# POWER.net
KiCad netlist of a schematic drawn in Altium Designer
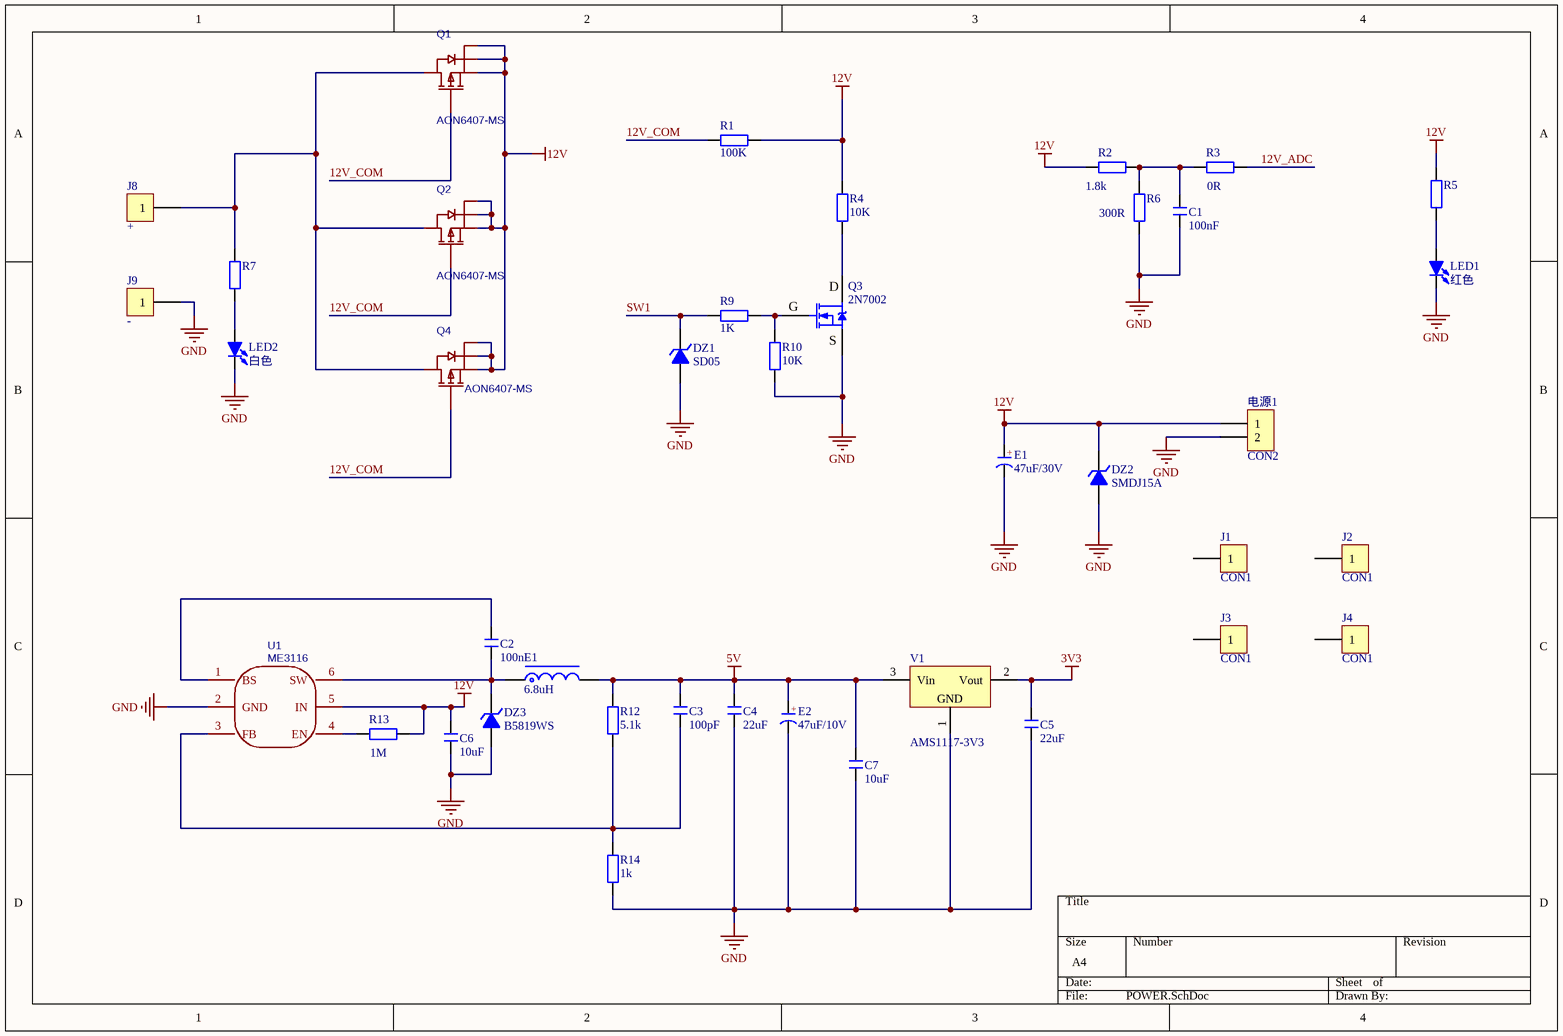
[diagram p0: POWER.SchDoc]

(export (version "E")
  (design (tool "Eeschema 10.0.6"))
  (components
    (comp (ref "C1")
      (value "100nF")
      (footprint "C 0805_L")
      (description "无极性贴片电容")
      (fields (field (name "版权归属") "源创客"))
      (libsource (lib "3.1   - 电阻-电容-电感") (part "C"))
    )
    (comp (ref "C2")
      (value "100nF")
      (footprint "C 0805_L")
      (description "无极性贴片电容")
      (fields (field (name "版权归属") "源创客"))
      (libsource (lib "3.1   - 电阻-电容-电感") (part "C"))
    )
    (comp (ref "C3")
      (value "100pF")
      (footprint "C 0805_L")
      (description "无极性贴片电容")
      (fields (field (name "版权归属") "源创客"))
      (libsource (lib "3.1   - 电阻-电容-电感") (part "C"))
    )
    (comp (ref "C4")
      (value "22uF")
      (footprint "C 0805_L")
      (description "无极性贴片电容")
      (fields (field (name "版权归属") "源创客"))
      (libsource (lib "3.1   - 电阻-电容-电感") (part "C"))
    )
    (comp (ref "C5")
      (value "22uF")
      (footprint "C 0805_L")
      (description "无极性贴片电容")
      (fields (field (name "版权归属") "源创客"))
      (libsource (lib "3.1   - 电阻-电容-电感") (part "C"))
    )
    (comp (ref "C6")
      (value "10uF")
      (footprint "C 0805_L")
      (description "无极性贴片电容")
      (fields (field (name "版权归属") "源创客"))
      (libsource (lib "3.1   - 电阻-电容-电感") (part "C"))
    )
    (comp (ref "C7")
      (value "10uF")
      (footprint "C 0805_L")
      (description "无极性贴片电容")
      (fields (field (name "版权归属") "源创客"))
      (libsource (lib "3.1   - 电阻-电容-电感") (part "C"))
    )
    (comp (ref "DZ1")
      (value "SD05")
      (footprint "SOD-323")
      (description "单向TVS 5V截止 峰值脉冲电流：17A              C502527")
      (fields (field (name "版权归属") "源创客"))
      (libsource (lib "8.1   - 二极管-整流桥") (part "1N4106"))
    )
    (comp (ref "DZ2")
      (value "SMDJ15A")
      (footprint "SMC")
      (description "TVS 15V截止 峰值浪涌电流：123A                   C438153")
      (fields (field (name "版权归属") "源创客"))
      (libsource (lib "8.1   - 二极管-整流桥") (part "1N4106"))
    )
    (comp (ref "DZ3")
      (value "B5819WS")
      (footprint "SOD-323")
      (description "电压:40V 电流:1A                                C7420331")
      (fields (field (name "版权归属") "源创客"))
      (libsource (lib "8.1   - 二极管-整流桥") (part "1N5256"))
    )
    (comp (ref "E1")
      (value "47uF/30V")
      (footprint "CM D(6.3*7.7)")
      (description "JVJ50V47M6x8                        47uF ±20% 50V                            C46550421")
      (fields (field (name "版权归属") "源创客"))
      (libsource (lib "3.1   - 电阻-电容-电感") (part "C-CS"))
    )
    (comp (ref "E2")
      (value "47uF/10V")
      (footprint "CM B(4*5.4)")
      (description "47uF ±20% 10V                           C48970978")
      (fields (field (name "版权归属") "源创客"))
      (libsource (lib "3.1   - 电阻-电容-电感") (part "C-CS"))
    )
    (comp (ref "J1") (value "CON1") (footprint "M3x5+6_L") (libsource (lib "常用元件库") (part "CON1")))
    (comp (ref "J2") (value "CON1") (footprint "M3x5+6_L") (libsource (lib "常用元件库") (part "CON1")))
    (comp (ref "J3") (value "CON1") (footprint "M3x5+6_L") (libsource (lib "常用元件库") (part "CON1")))
    (comp (ref "J4") (value "CON1") (footprint "M3x5+6_L") (libsource (lib "常用元件库") (part "CON1")))
    (comp (ref "J8") (value "+") (footprint "HDR2.54-LI-1P") (libsource (lib "") (part "CON1_1")))
    (comp (ref "J9") (value "-") (footprint "HDR2.54-LI-1P") (libsource (lib "") (part "CON1_1")))
    (comp (ref "L1")
      (value "6.8uH")
      (footprint "CD42")
      (description "YP0402-6R8M                          C576569")
      (fields (field (name "版权归属") "源创客"))
      (libsource (lib "3.1   - 电阻-电容-电感") (part "L-CD"))
    )
    (comp (ref "LED1")
      (value "红色")
      (footprint "LED 0805R")
      (description "贴片LED")
      (fields (field (name "版权归属") "源创客"))
      (libsource (lib "9.1   - LED") (part "LED-SMD"))
    )
    (comp (ref "LED2")
      (value "白色")
      (footprint "LED 0805B")
      (description "贴片LED")
      (fields (field (name "版权归属") "源创客"))
      (libsource (lib "9.1   - LED") (part "LED-SMD"))
    )
    (comp (ref "Q1")
      (value "AON6407-MS")
      (footprint "TDSON-8_L5.9-W5.2-P1.27-BL")
      (fields (field (name "MANUFACTURER") "MSKSEMI(美森科)") (field (name "CONTRIBUTOR") "lcsc"))
      (libsource (lib "altium-import") (part "root_1_AON6407-MS_"))
    )
    (comp (ref "Q2")
      (value "AON6407-MS")
      (footprint "TDSON-8_L5.9-W5.2-P1.27-BL")
      (fields (field (name "MANUFACTURER") "MSKSEMI(美森科)") (field (name "CONTRIBUTOR") "lcsc"))
      (libsource (lib "altium-import") (part "root_1_AON6407-MS_"))
    )
    (comp (ref "Q3")
      (value "2N7002")
      (footprint "SOT-23")
      (description "N沟场效应管")
      (fields (field (name "版权归属") "源创客"))
      (libsource (lib "6.1   - 场效应管-可控硅") (part "IRF840"))
    )
    (comp (ref "Q4")
      (value "AON6407-MS")
      (footprint "TDSON-8_L5.9-W5.2-P1.27-BL")
      (fields (field (name "MANUFACTURER") "MSKSEMI(美森科)") (field (name "CONTRIBUTOR") "lcsc"))
      (libsource (lib "altium-import") (part "root_1_AON6407-MS_"))
    )
    (comp (ref "R1")
      (value "100K")
      (footprint "R 0805_L")
      (description "贴片电阻")
      (fields (field (name "版权归属") "源创客"))
      (libsource (lib "3.1   - 电阻-电容-电感") (part "R"))
    )
    (comp (ref "R2")
      (value "1.8k")
      (footprint "R 0805_L")
      (description "贴片电阻")
      (fields (field (name "版权归属") "源创客"))
      (libsource (lib "3.1   - 电阻-电容-电感") (part "R"))
    )
    (comp (ref "R3")
      (value "0R")
      (footprint "R 0805_L")
      (description "贴片电阻")
      (fields (field (name "版权归属") "源创客"))
      (libsource (lib "3.1   - 电阻-电容-电感") (part "R"))
    )
    (comp (ref "R4")
      (value "10K")
      (footprint "R 0805_L")
      (description "贴片电阻")
      (fields (field (name "版权归属") "源创客"))
      (libsource (lib "3.1   - 电阻-电容-电感") (part "R"))
    )
    (comp (ref "R5")
      (value "~")
      (footprint "R 0805_L")
      (description "贴片电阻")
      (fields (field (name "版权归属") "源创客"))
      (libsource (lib "3.1   - 电阻-电容-电感") (part "R"))
    )
    (comp (ref "R6")
      (value "300R")
      (footprint "R 0805_L")
      (description "贴片电阻")
      (fields (field (name "版权归属") "源创客"))
      (libsource (lib "3.1   - 电阻-电容-电感") (part "R"))
    )
    (comp (ref "R7")
      (value "~")
      (footprint "R 0805_L")
      (description "贴片电阻")
      (fields (field (name "版权归属") "源创客"))
      (libsource (lib "3.1   - 电阻-电容-电感") (part "R"))
    )
    (comp (ref "R9")
      (value "1K")
      (footprint "R 0805_L")
      (description "贴片电阻")
      (fields (field (name "版权归属") "源创客"))
      (libsource (lib "3.1   - 电阻-电容-电感") (part "R"))
    )
    (comp (ref "R10")
      (value "10K")
      (footprint "R 0805_L")
      (description "贴片电阻")
      (fields (field (name "版权归属") "源创客"))
      (libsource (lib "3.1   - 电阻-电容-电感") (part "R"))
    )
    (comp (ref "R12")
      (value "5.1k")
      (footprint "R 0805_L")
      (description "贴片电阻")
      (fields (field (name "版权归属") "源创客"))
      (libsource (lib "3.1   - 电阻-电容-电感") (part "R"))
    )
    (comp (ref "R13")
      (value "1M")
      (footprint "R 0805_L")
      (description "贴片电阻")
      (fields (field (name "版权归属") "源创客"))
      (libsource (lib "3.1   - 电阻-电容-电感") (part "R"))
    )
    (comp (ref "R14")
      (value "1k")
      (footprint "R 0805_L")
      (description "贴片电阻")
      (fields (field (name "版权归属") "源创客"))
      (libsource (lib "3.1   - 电阻-电容-电感") (part "R"))
    )
    (comp (ref "U1")
      (value "ME3116")
      (footprint "SOT23-6")
      (fields (field (name "MANUFACTURER") "MICRONE(南京微盟)") (field (name "MANUFACTURER PART") "ME3116AM6G"))
      (libsource (lib "altium-import") (part "root_0_ME3116_"))
    )
    (comp (ref "V1")
      (value "AMS1117-3V3")
      (footprint "SOT-223")
      (description "三端稳压芯片")
      (fields (field (name "版权归属") "源创客"))
      (libsource (lib "1.3   - 电源类芯片") (part "AMS1117"))
    )
    (comp (ref "电源1")
      (value "CON2")
      (footprint "TX60PW-M20")
      (description "Connector")
      (libsource (lib "插件") (part "CON2"))
    )
  )
  (nets
    (net (code "1") (name "/12V_ADC") (class "Default")
      (node (ref "R3") (pin "2") (pinfunction "2_2") (pintype "passive"))
    )
    (net (code "2") (name "/12V_COM") (class "Default")
      (node (ref "Q1") (pin "4") (pinfunction "G_4") (pintype "passive"))
      (node (ref "Q2") (pin "4") (pinfunction "G_4") (pintype "passive"))
      (node (ref "Q4") (pin "4") (pinfunction "G_4") (pintype "passive"))
      (node (ref "R1") (pin "2") (pinfunction "2_2") (pintype "passive"))
    )
    (net (code "3") (name "/SW1") (class "Default")
      (node (ref "DZ1") (pin "2") (pinfunction "K_2") (pintype "passive"))
      (node (ref "R9") (pin "1") (pinfunction "1_1") (pintype "passive"))
    )
    (net (code "4") (name "3V3") (class "Default")
      (node (ref "C5") (pin "2") (pinfunction "2_2") (pintype "passive"))
      (node (ref "V1") (pin "2") (pinfunction "Vout_2") (pintype "passive"))
    )
    (net (code "5") (name "5V") (class "Default")
      (node (ref "C3") (pin "2") (pinfunction "2_2") (pintype "passive"))
      (node (ref "C4") (pin "2") (pinfunction "2_2") (pintype "passive"))
      (node (ref "C7") (pin "2") (pinfunction "2_2") (pintype "passive"))
      (node (ref "E2") (pin "1") (pinfunction "A_1") (pintype "passive"))
      (node (ref "L1") (pin "2") (pinfunction "2_2") (pintype "passive"))
      (node (ref "R12") (pin "2") (pinfunction "2_2") (pintype "passive"))
      (node (ref "V1") (pin "3") (pinfunction "Vin_3") (pintype "passive"))
    )
    (net (code "6") (name "12V") (class "Default")
      (node (ref "C6") (pin "2") (pinfunction "2_2") (pintype "passive"))
      (node (ref "DZ2") (pin "2") (pinfunction "K_2") (pintype "passive"))
      (node (ref "E1") (pin "1") (pinfunction "A_1") (pintype "passive"))
      (node (ref "Q1") (pin "1") (pinfunction "S_1") (pintype "passive"))
      (node (ref "Q1") (pin "2") (pinfunction "S_2") (pintype "passive"))
      (node (ref "Q1") (pin "3") (pinfunction "S_3") (pintype "passive"))
      (node (ref "Q2") (pin "1") (pinfunction "S_1") (pintype "passive"))
      (node (ref "Q2") (pin "2") (pinfunction "S_2") (pintype "passive"))
      (node (ref "Q2") (pin "3") (pinfunction "S_3") (pintype "passive"))
      (node (ref "Q4") (pin "1") (pinfunction "S_1") (pintype "passive"))
      (node (ref "Q4") (pin "2") (pinfunction "S_2") (pintype "passive"))
      (node (ref "Q4") (pin "3") (pinfunction "S_3") (pintype "passive"))
      (node (ref "R1") (pin "1") (pinfunction "1_1") (pintype "passive"))
      (node (ref "R13") (pin "1") (pinfunction "1_1") (pintype "passive"))
      (node (ref "R2") (pin "2") (pinfunction "2_2") (pintype "passive"))
      (node (ref "R4") (pin "2") (pinfunction "2_2") (pintype "passive"))
      (node (ref "R5") (pin "1") (pinfunction "1_1") (pintype "passive"))
      (node (ref "U1") (pin "5") (pinfunction "IN_5") (pintype "passive"))
      (node (ref "电源1") (pin "1") (pinfunction "1_1") (pintype "passive"))
    )
    (net (code "7") (name "GND") (class "Default")
      (node (ref "C1") (pin "1") (pinfunction "1_1") (pintype "passive"))
      (node (ref "C4") (pin "1") (pinfunction "1_1") (pintype "passive"))
      (node (ref "C5") (pin "1") (pinfunction "1_1") (pintype "passive"))
      (node (ref "C6") (pin "1") (pinfunction "1_1") (pintype "passive"))
      (node (ref "C7") (pin "1") (pinfunction "1_1") (pintype "passive"))
      (node (ref "DZ1") (pin "1") (pinfunction "A_1") (pintype "passive"))
      (node (ref "DZ2") (pin "1") (pinfunction "A_1") (pintype "passive"))
      (node (ref "DZ3") (pin "1") (pinfunction "A_1") (pintype "passive"))
      (node (ref "E1") (pin "2") (pinfunction "K_2") (pintype "passive"))
      (node (ref "E2") (pin "2") (pinfunction "K_2") (pintype "passive"))
      (node (ref "J9") (pin "1") (pinfunction "1_1") (pintype "passive"))
      (node (ref "LED1") (pin "2") (pinfunction "K_2") (pintype "passive"))
      (node (ref "LED2") (pin "2") (pinfunction "K_2") (pintype "passive"))
      (node (ref "Q3") (pin "3") (pinfunction "S_3") (pintype "passive"))
      (node (ref "R10") (pin "1") (pinfunction "1_1") (pintype "passive"))
      (node (ref "R14") (pin "1") (pinfunction "1_1") (pintype "passive"))
      (node (ref "R6") (pin "2") (pinfunction "2_2") (pintype "passive"))
      (node (ref "U1") (pin "2") (pinfunction "GND_2") (pintype "passive"))
      (node (ref "V1") (pin "1") (pinfunction "GND_1") (pintype "passive"))
      (node (ref "电源1") (pin "2") (pinfunction "2_2") (pintype "passive"))
    )
    (net (code "8") (name "Net-(C1-Pad2)") (class "Default")
      (node (ref "C1") (pin "2") (pinfunction "2_2") (pintype "passive"))
      (node (ref "R2") (pin "1") (pinfunction "1_1") (pintype "passive"))
      (node (ref "R3") (pin "1") (pinfunction "1_1") (pintype "passive"))
      (node (ref "R6") (pin "1") (pinfunction "1_1") (pintype "passive"))
    )
    (net (code "9") (name "Net-(DZ3-K)") (class "Default")
      (node (ref "C2") (pin "1") (pinfunction "1_1") (pintype "passive"))
      (node (ref "DZ3") (pin "2") (pinfunction "K_2") (pintype "passive"))
      (node (ref "L1") (pin "1") (pinfunction "1_1") (pintype "passive"))
      (node (ref "U1") (pin "6") (pinfunction "SW_6") (pintype "passive"))
    )
    (net (code "10") (name "Net-(LED1-A)") (class "Default")
      (node (ref "LED1") (pin "1") (pinfunction "A_1") (pintype "passive"))
      (node (ref "R5") (pin "2") (pinfunction "2_2") (pintype "passive"))
    )
    (net (code "11") (name "Net-(LED2-A)") (class "Default")
      (node (ref "LED2") (pin "1") (pinfunction "A_1") (pintype "passive"))
      (node (ref "R7") (pin "2") (pinfunction "2_2") (pintype "passive"))
    )
    (net (code "12") (name "Net-(Q1-D)") (class "Default")
      (node (ref "J8") (pin "1") (pinfunction "1_1") (pintype "passive"))
      (node (ref "Q1") (pin "5") (pinfunction "D_5") (pintype "passive"))
      (node (ref "Q2") (pin "5") (pinfunction "D_5") (pintype "passive"))
      (node (ref "Q4") (pin "5") (pinfunction "D_5") (pintype "passive"))
      (node (ref "R7") (pin "1") (pinfunction "1_1") (pintype "passive"))
    )
    (net (code "13") (name "Net-(Q3-D)") (class "Default")
      (node (ref "Q3") (pin "2") (pinfunction "D_2") (pintype "passive"))
      (node (ref "R4") (pin "1") (pinfunction "1_1") (pintype "passive"))
    )
    (net (code "14") (name "Net-(Q3-G)") (class "Default")
      (node (ref "Q3") (pin "1") (pinfunction "G_1") (pintype "passive"))
      (node (ref "R10") (pin "2") (pinfunction "2_2") (pintype "passive"))
      (node (ref "R9") (pin "2") (pinfunction "2_2") (pintype "passive"))
    )
    (net (code "15") (name "Net-(U1-BS)") (class "Default")
      (node (ref "C2") (pin "2") (pinfunction "2_2") (pintype "passive"))
      (node (ref "U1") (pin "1") (pinfunction "BS_1") (pintype "passive"))
    )
    (net (code "16") (name "Net-(U1-EN)") (class "Default")
      (node (ref "R13") (pin "2") (pinfunction "2_2") (pintype "passive"))
      (node (ref "U1") (pin "4") (pinfunction "EN_4") (pintype "passive"))
    )
    (net (code "17") (name "Net-(U1-FB)") (class "Default")
      (node (ref "C3") (pin "1") (pinfunction "1_1") (pintype "passive"))
      (node (ref "R12") (pin "1") (pinfunction "1_1") (pintype "passive"))
      (node (ref "R14") (pin "2") (pinfunction "2_2") (pintype "passive"))
      (node (ref "U1") (pin "3") (pinfunction "FB_3") (pintype "passive"))
    )
    (net (code "18") (name "unconnected-(J1-Pad1)") (class "Default")
      (node (ref "J1") (pin "1") (pinfunction "1_1") (pintype "passive"))
    )
    (net (code "19") (name "unconnected-(J2-Pad1)") (class "Default")
      (node (ref "J2") (pin "1") (pinfunction "1_1") (pintype "passive"))
    )
    (net (code "20") (name "unconnected-(J3-Pad1)") (class "Default")
      (node (ref "J3") (pin "1") (pinfunction "1_1") (pintype "passive"))
    )
    (net (code "21") (name "unconnected-(J4-Pad1)") (class "Default")
      (node (ref "J4") (pin "1") (pinfunction "1_1") (pintype "passive"))
    )
  )
)
